# Rubik_servos_2.net
KiCad netlist of a schematic drawn in EAGLE
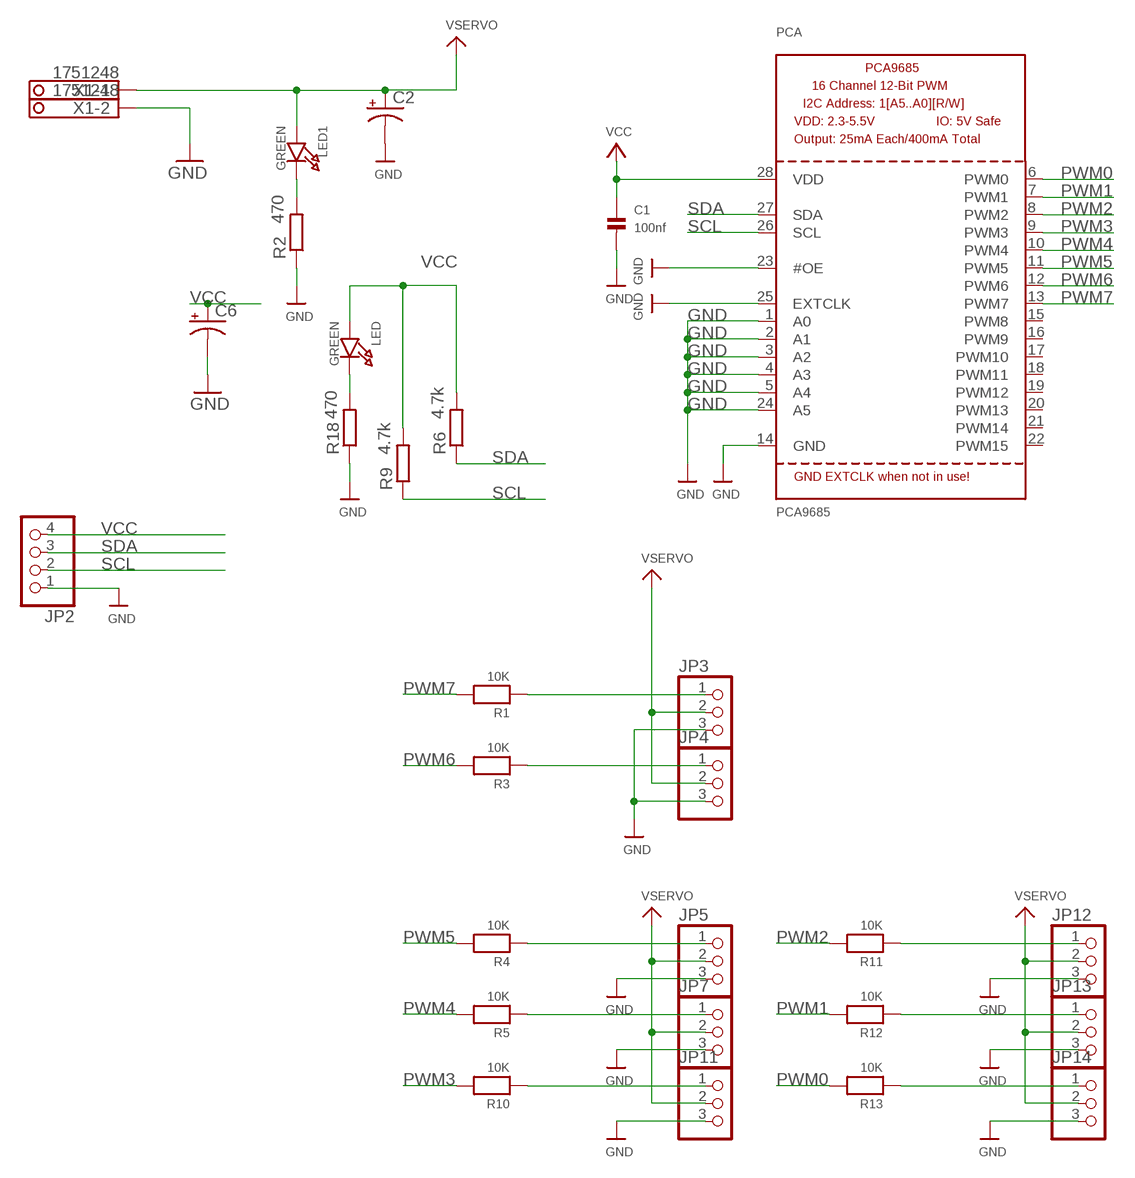
[diagram p0: schematic, sheet 1]

(export (version "E")
  (design (tool "Eeschema 10.0.6"))
  (components
    (comp (ref "C1")
      (value "100nf")
      (footprint "eagle-import:0805")
      (libsource (lib "eagle-import") (part "CAP_CERAMIC0805"))
    )
    (comp (ref "C2")
      (value "CPOL-USE3.5-8")
      (footprint "eagle-import:E3,5-8")
      (libsource (lib "eagle-import") (part "CPOL-USE3.5-8"))
    )
    (comp (ref "C6")
      (value "CAP_POL3528")
      (footprint "eagle-import:EIA3528")
      (libsource (lib "eagle-import") (part "CAP_POL3528"))
    )
    (comp (ref "JP2")
      (value "PINHD-1X4\"")
      (footprint "eagle-import:1X04")
      (libsource (lib "eagle-import") (part "PINHD-1X4{dblquote}"))
    )
    (comp (ref "JP3")
      (value "PINHD-1X3CB")
      (footprint "eagle-import:1X03-CLEANBIG")
      (libsource (lib "eagle-import") (part "PINHD-1X3CB"))
    )
    (comp (ref "JP4")
      (value "PINHD-1X3CB")
      (footprint "eagle-import:1X03-CLEANBIG")
      (libsource (lib "eagle-import") (part "PINHD-1X3CB"))
    )
    (comp (ref "JP5")
      (value "PINHD-1X3CB")
      (footprint "eagle-import:1X03-CLEANBIG")
      (libsource (lib "eagle-import") (part "PINHD-1X3CB"))
    )
    (comp (ref "JP7")
      (value "PINHD-1X3CB")
      (footprint "eagle-import:1X03-CLEANBIG")
      (libsource (lib "eagle-import") (part "PINHD-1X3CB"))
    )
    (comp (ref "JP11")
      (value "PINHD-1X3CB")
      (footprint "eagle-import:1X03-CLEANBIG")
      (libsource (lib "eagle-import") (part "PINHD-1X3CB"))
    )
    (comp (ref "JP12")
      (value "PINHD-1X3CB")
      (footprint "eagle-import:1X03-CLEANBIG")
      (libsource (lib "eagle-import") (part "PINHD-1X3CB"))
    )
    (comp (ref "JP13")
      (value "PINHD-1X3CB")
      (footprint "eagle-import:1X03-CLEANBIG")
      (libsource (lib "eagle-import") (part "PINHD-1X3CB"))
    )
    (comp (ref "JP14")
      (value "PINHD-1X3CB")
      (footprint "eagle-import:1X03-CLEANBIG")
      (libsource (lib "eagle-import") (part "PINHD-1X3CB"))
    )
    (comp (ref "LED")
      (value "GREEN")
      (footprint "eagle-import:CHIPLED_0805")
      (libsource (lib "eagle-import") (part "LED0805"))
    )
    (comp (ref "LED1")
      (value "GREEN")
      (footprint "eagle-import:CHIPLED_0805")
      (libsource (lib "eagle-import") (part "LED0805"))
    )
    (comp (ref "PCA")
      (value "PCA9685")
      (footprint "eagle-import:TSSOP28")
      (libsource (lib "eagle-import") (part "PCA9685"))
    )
    (comp (ref "R1")
      (value "10K")
      (footprint "eagle-import:0603")
      (libsource (lib "eagle-import") (part "RESISTOR0603"))
    )
    (comp (ref "R2")
      (value "470")
      (footprint "eagle-import:R0805")
      (libsource (lib "eagle-import") (part "R-EU_R0805"))
    )
    (comp (ref "R3")
      (value "10K")
      (footprint "eagle-import:0603")
      (libsource (lib "eagle-import") (part "RESISTOR0603"))
    )
    (comp (ref "R4")
      (value "10K")
      (footprint "eagle-import:0603")
      (libsource (lib "eagle-import") (part "RESISTOR0603"))
    )
    (comp (ref "R5")
      (value "10K")
      (footprint "eagle-import:0603")
      (libsource (lib "eagle-import") (part "RESISTOR0603"))
    )
    (comp (ref "R6")
      (value "4.7k")
      (footprint "eagle-import:R0603")
      (libsource (lib "eagle-import") (part "R-EU_R0603"))
    )
    (comp (ref "R9")
      (value "4.7k")
      (footprint "eagle-import:R0603")
      (libsource (lib "eagle-import") (part "R-EU_R0603"))
    )
    (comp (ref "R10")
      (value "10K")
      (footprint "eagle-import:0603")
      (libsource (lib "eagle-import") (part "RESISTOR0603"))
    )
    (comp (ref "R11")
      (value "10K")
      (footprint "eagle-import:0603")
      (libsource (lib "eagle-import") (part "RESISTOR0603"))
    )
    (comp (ref "R12")
      (value "10K")
      (footprint "eagle-import:0603")
      (libsource (lib "eagle-import") (part "RESISTOR0603"))
    )
    (comp (ref "R13")
      (value "10K")
      (footprint "eagle-import:0603")
      (libsource (lib "eagle-import") (part "RESISTOR0603"))
    )
    (comp (ref "R18")
      (value "470")
      (footprint "eagle-import:R0805")
      (libsource (lib "eagle-import") (part "R-EU_R0805"))
    )
    (comp (ref "X1")
      (value "1751248")
      (footprint "eagle-import:1751248")
      (libsource (lib "eagle-import") (part "1751248"))
    )
  )
  (nets
    (net (code "1") (name "/PWM0") (class "Default")
      (node (ref "PCA") (pin "6") (pinfunction "PWM0_6") (pintype "output"))
      (node (ref "R13") (pin "2") (pinfunction "2_2") (pintype "passive"))
    )
    (net (code "2") (name "/PWM1") (class "Default")
      (node (ref "PCA") (pin "7") (pinfunction "PWM1_7") (pintype "output"))
      (node (ref "R12") (pin "2") (pinfunction "2_2") (pintype "passive"))
    )
    (net (code "3") (name "/PWM2") (class "Default")
      (node (ref "PCA") (pin "8") (pinfunction "PWM2_8") (pintype "output"))
      (node (ref "R11") (pin "2") (pinfunction "2_2") (pintype "passive"))
    )
    (net (code "4") (name "/PWM3") (class "Default")
      (node (ref "PCA") (pin "9") (pinfunction "PWM3_9") (pintype "output"))
      (node (ref "R10") (pin "2") (pinfunction "2_2") (pintype "passive"))
    )
    (net (code "5") (name "/PWM4") (class "Default")
      (node (ref "PCA") (pin "10") (pinfunction "PWM4_10") (pintype "output"))
      (node (ref "R5") (pin "2") (pinfunction "2_2") (pintype "passive"))
    )
    (net (code "6") (name "/PWM5") (class "Default")
      (node (ref "PCA") (pin "11") (pinfunction "PWM5_11") (pintype "output"))
      (node (ref "R4") (pin "2") (pinfunction "2_2") (pintype "passive"))
    )
    (net (code "7") (name "/PWM6") (class "Default")
      (node (ref "PCA") (pin "12") (pinfunction "PWM6_12") (pintype "output"))
      (node (ref "R3") (pin "2") (pinfunction "2_2") (pintype "passive"))
    )
    (net (code "8") (name "/PWM7") (class "Default")
      (node (ref "PCA") (pin "13") (pinfunction "PWM7_13") (pintype "output"))
      (node (ref "R1") (pin "2") (pinfunction "2_2") (pintype "passive"))
    )
    (net (code "9") (name "/SCL") (class "Default")
      (node (ref "JP2") (pin "2") (pinfunction "2_2") (pintype "passive"))
      (node (ref "PCA") (pin "26") (pinfunction "SCL_26") (pintype "bidirectional"))
      (node (ref "R9") (pin "1") (pinfunction "1_1") (pintype "passive"))
    )
    (net (code "10") (name "/SDA") (class "Default")
      (node (ref "JP2") (pin "3") (pinfunction "3_3") (pintype "passive"))
      (node (ref "PCA") (pin "27") (pinfunction "SDA_27") (pintype "bidirectional"))
      (node (ref "R6") (pin "1") (pinfunction "1_1") (pintype "passive"))
    )
    (net (code "11") (name "GND") (class "Default")
      (node (ref "C1") (pin "2") (pinfunction "P$2_2") (pintype "passive"))
      (node (ref "C2") (pin "-") (pinfunction "-_-") (pintype "passive"))
      (node (ref "C6") (pin "C") (pinfunction "-_C") (pintype "passive"))
      (node (ref "JP11") (pin "3") (pinfunction "3_3") (pintype "passive"))
      (node (ref "JP12") (pin "3") (pinfunction "3_3") (pintype "passive"))
      (node (ref "JP13") (pin "3") (pinfunction "3_3") (pintype "passive"))
      (node (ref "JP14") (pin "3") (pinfunction "3_3") (pintype "passive"))
      (node (ref "JP2") (pin "1") (pinfunction "1_1") (pintype "passive"))
      (node (ref "JP3") (pin "3") (pinfunction "3_3") (pintype "passive"))
      (node (ref "JP4") (pin "3") (pinfunction "3_3") (pintype "passive"))
      (node (ref "JP5") (pin "3") (pinfunction "3_3") (pintype "passive"))
      (node (ref "JP7") (pin "3") (pinfunction "3_3") (pintype "passive"))
      (node (ref "PCA") (pin "1") (pinfunction "A0_1") (pintype "bidirectional"))
      (node (ref "PCA") (pin "14") (pinfunction "GND_14") (pintype "power_in"))
      (node (ref "PCA") (pin "2") (pinfunction "A1_2") (pintype "bidirectional"))
      (node (ref "PCA") (pin "23") (pinfunction "#OE_23") (pintype "input"))
      (node (ref "PCA") (pin "24") (pinfunction "A5_24") (pintype "bidirectional"))
      (node (ref "PCA") (pin "25") (pinfunction "EXTCLK_25") (pintype "input"))
      (node (ref "PCA") (pin "3") (pinfunction "A2_3") (pintype "bidirectional"))
      (node (ref "PCA") (pin "4") (pinfunction "A3_4") (pintype "bidirectional"))
      (node (ref "PCA") (pin "5") (pinfunction "A4_5") (pintype "bidirectional"))
      (node (ref "R18") (pin "1") (pinfunction "1_1") (pintype "passive"))
      (node (ref "R2") (pin "1") (pinfunction "1_1") (pintype "passive"))
      (node (ref "X1") (pin "2") (pinfunction "K_2") (pintype "passive"))
    )
    (net (code "12") (name "Net-(JP3-Pad1)") (class "Default")
      (node (ref "JP3") (pin "1") (pinfunction "1_1") (pintype "passive"))
      (node (ref "R1") (pin "1") (pinfunction "1_1") (pintype "passive"))
    )
    (net (code "13") (name "Net-(JP4-Pad1)") (class "Default")
      (node (ref "JP4") (pin "1") (pinfunction "1_1") (pintype "passive"))
      (node (ref "R3") (pin "1") (pinfunction "1_1") (pintype "passive"))
    )
    (net (code "14") (name "Net-(JP5-Pad1)") (class "Default")
      (node (ref "JP5") (pin "1") (pinfunction "1_1") (pintype "passive"))
      (node (ref "R4") (pin "1") (pinfunction "1_1") (pintype "passive"))
    )
    (net (code "15") (name "Net-(JP7-Pad1)") (class "Default")
      (node (ref "JP7") (pin "1") (pinfunction "1_1") (pintype "passive"))
      (node (ref "R5") (pin "1") (pinfunction "1_1") (pintype "passive"))
    )
    (net (code "16") (name "Net-(JP11-Pad1)") (class "Default")
      (node (ref "JP11") (pin "1") (pinfunction "1_1") (pintype "passive"))
      (node (ref "R10") (pin "1") (pinfunction "1_1") (pintype "passive"))
    )
    (net (code "17") (name "Net-(JP12-Pad1)") (class "Default")
      (node (ref "JP12") (pin "1") (pinfunction "1_1") (pintype "passive"))
      (node (ref "R11") (pin "1") (pinfunction "1_1") (pintype "passive"))
    )
    (net (code "18") (name "Net-(JP13-Pad1)") (class "Default")
      (node (ref "JP13") (pin "1") (pinfunction "1_1") (pintype "passive"))
      (node (ref "R12") (pin "1") (pinfunction "1_1") (pintype "passive"))
    )
    (net (code "19") (name "Net-(JP14-Pad1)") (class "Default")
      (node (ref "JP14") (pin "1") (pinfunction "1_1") (pintype "passive"))
      (node (ref "R13") (pin "1") (pinfunction "1_1") (pintype "passive"))
    )
    (net (code "20") (name "Net-(LED-PadC)") (class "Default")
      (node (ref "LED") (pin "C") (pinfunction "C_C") (pintype "passive"))
      (node (ref "R18") (pin "2") (pinfunction "2_2") (pintype "passive"))
    )
    (net (code "21") (name "Net-(LED1-PadC)") (class "Default")
      (node (ref "LED1") (pin "C") (pinfunction "C_C") (pintype "passive"))
      (node (ref "R2") (pin "2") (pinfunction "2_2") (pintype "passive"))
    )
    (net (code "22") (name "VCC") (class "Default")
      (node (ref "C1") (pin "1") (pinfunction "P$1_1") (pintype "passive"))
      (node (ref "C6") (pin "A") (pinfunction "+_A") (pintype "passive"))
      (node (ref "JP2") (pin "4") (pinfunction "4_4") (pintype "passive"))
      (node (ref "LED") (pin "A") (pinfunction "A_A") (pintype "passive"))
      (node (ref "PCA") (pin "28") (pinfunction "VDD_28") (pintype "power_in"))
      (node (ref "R6") (pin "2") (pinfunction "2_2") (pintype "passive"))
      (node (ref "R9") (pin "2") (pinfunction "2_2") (pintype "passive"))
    )
    (net (code "23") (name "VSERVO") (class "Default")
      (node (ref "C2") (pin "+") (pinfunction "+_+") (pintype "passive"))
      (node (ref "JP11") (pin "2") (pinfunction "2_2") (pintype "passive"))
      (node (ref "JP12") (pin "2") (pinfunction "2_2") (pintype "passive"))
      (node (ref "JP13") (pin "2") (pinfunction "2_2") (pintype "passive"))
      (node (ref "JP14") (pin "2") (pinfunction "2_2") (pintype "passive"))
      (node (ref "JP3") (pin "2") (pinfunction "2_2") (pintype "passive"))
      (node (ref "JP4") (pin "2") (pinfunction "2_2") (pintype "passive"))
      (node (ref "JP5") (pin "2") (pinfunction "2_2") (pintype "passive"))
      (node (ref "JP7") (pin "2") (pinfunction "2_2") (pintype "passive"))
      (node (ref "LED1") (pin "A") (pinfunction "A_A") (pintype "passive"))
      (node (ref "X1") (pin "1") (pinfunction "K_1") (pintype "passive"))
    )
    (net (code "24") (name "unconnected-(PCA-PWM8-Pad15)") (class "Default")
      (node (ref "PCA") (pin "15") (pinfunction "PWM8_15") (pintype "output"))
    )
    (net (code "25") (name "unconnected-(PCA-PWM9-Pad16)") (class "Default")
      (node (ref "PCA") (pin "16") (pinfunction "PWM9_16") (pintype "output"))
    )
    (net (code "26") (name "unconnected-(PCA-PWM10-Pad17)") (class "Default")
      (node (ref "PCA") (pin "17") (pinfunction "PWM10_17") (pintype "output"))
    )
    (net (code "27") (name "unconnected-(PCA-PWM11-Pad18)") (class "Default")
      (node (ref "PCA") (pin "18") (pinfunction "PWM11_18") (pintype "output"))
    )
    (net (code "28") (name "unconnected-(PCA-PWM12-Pad19)") (class "Default")
      (node (ref "PCA") (pin "19") (pinfunction "PWM12_19") (pintype "output"))
    )
    (net (code "29") (name "unconnected-(PCA-PWM13-Pad20)") (class "Default")
      (node (ref "PCA") (pin "20") (pinfunction "PWM13_20") (pintype "output"))
    )
    (net (code "30") (name "unconnected-(PCA-PWM14-Pad21)") (class "Default")
      (node (ref "PCA") (pin "21") (pinfunction "PWM14_21") (pintype "output"))
    )
    (net (code "31") (name "unconnected-(PCA-PWM15-Pad22)") (class "Default")
      (node (ref "PCA") (pin "22") (pinfunction "PWM15_22") (pintype "output"))
    )
  )
)
